# microsd.net
KiCad netlist of a schematic drawn in EAGLE
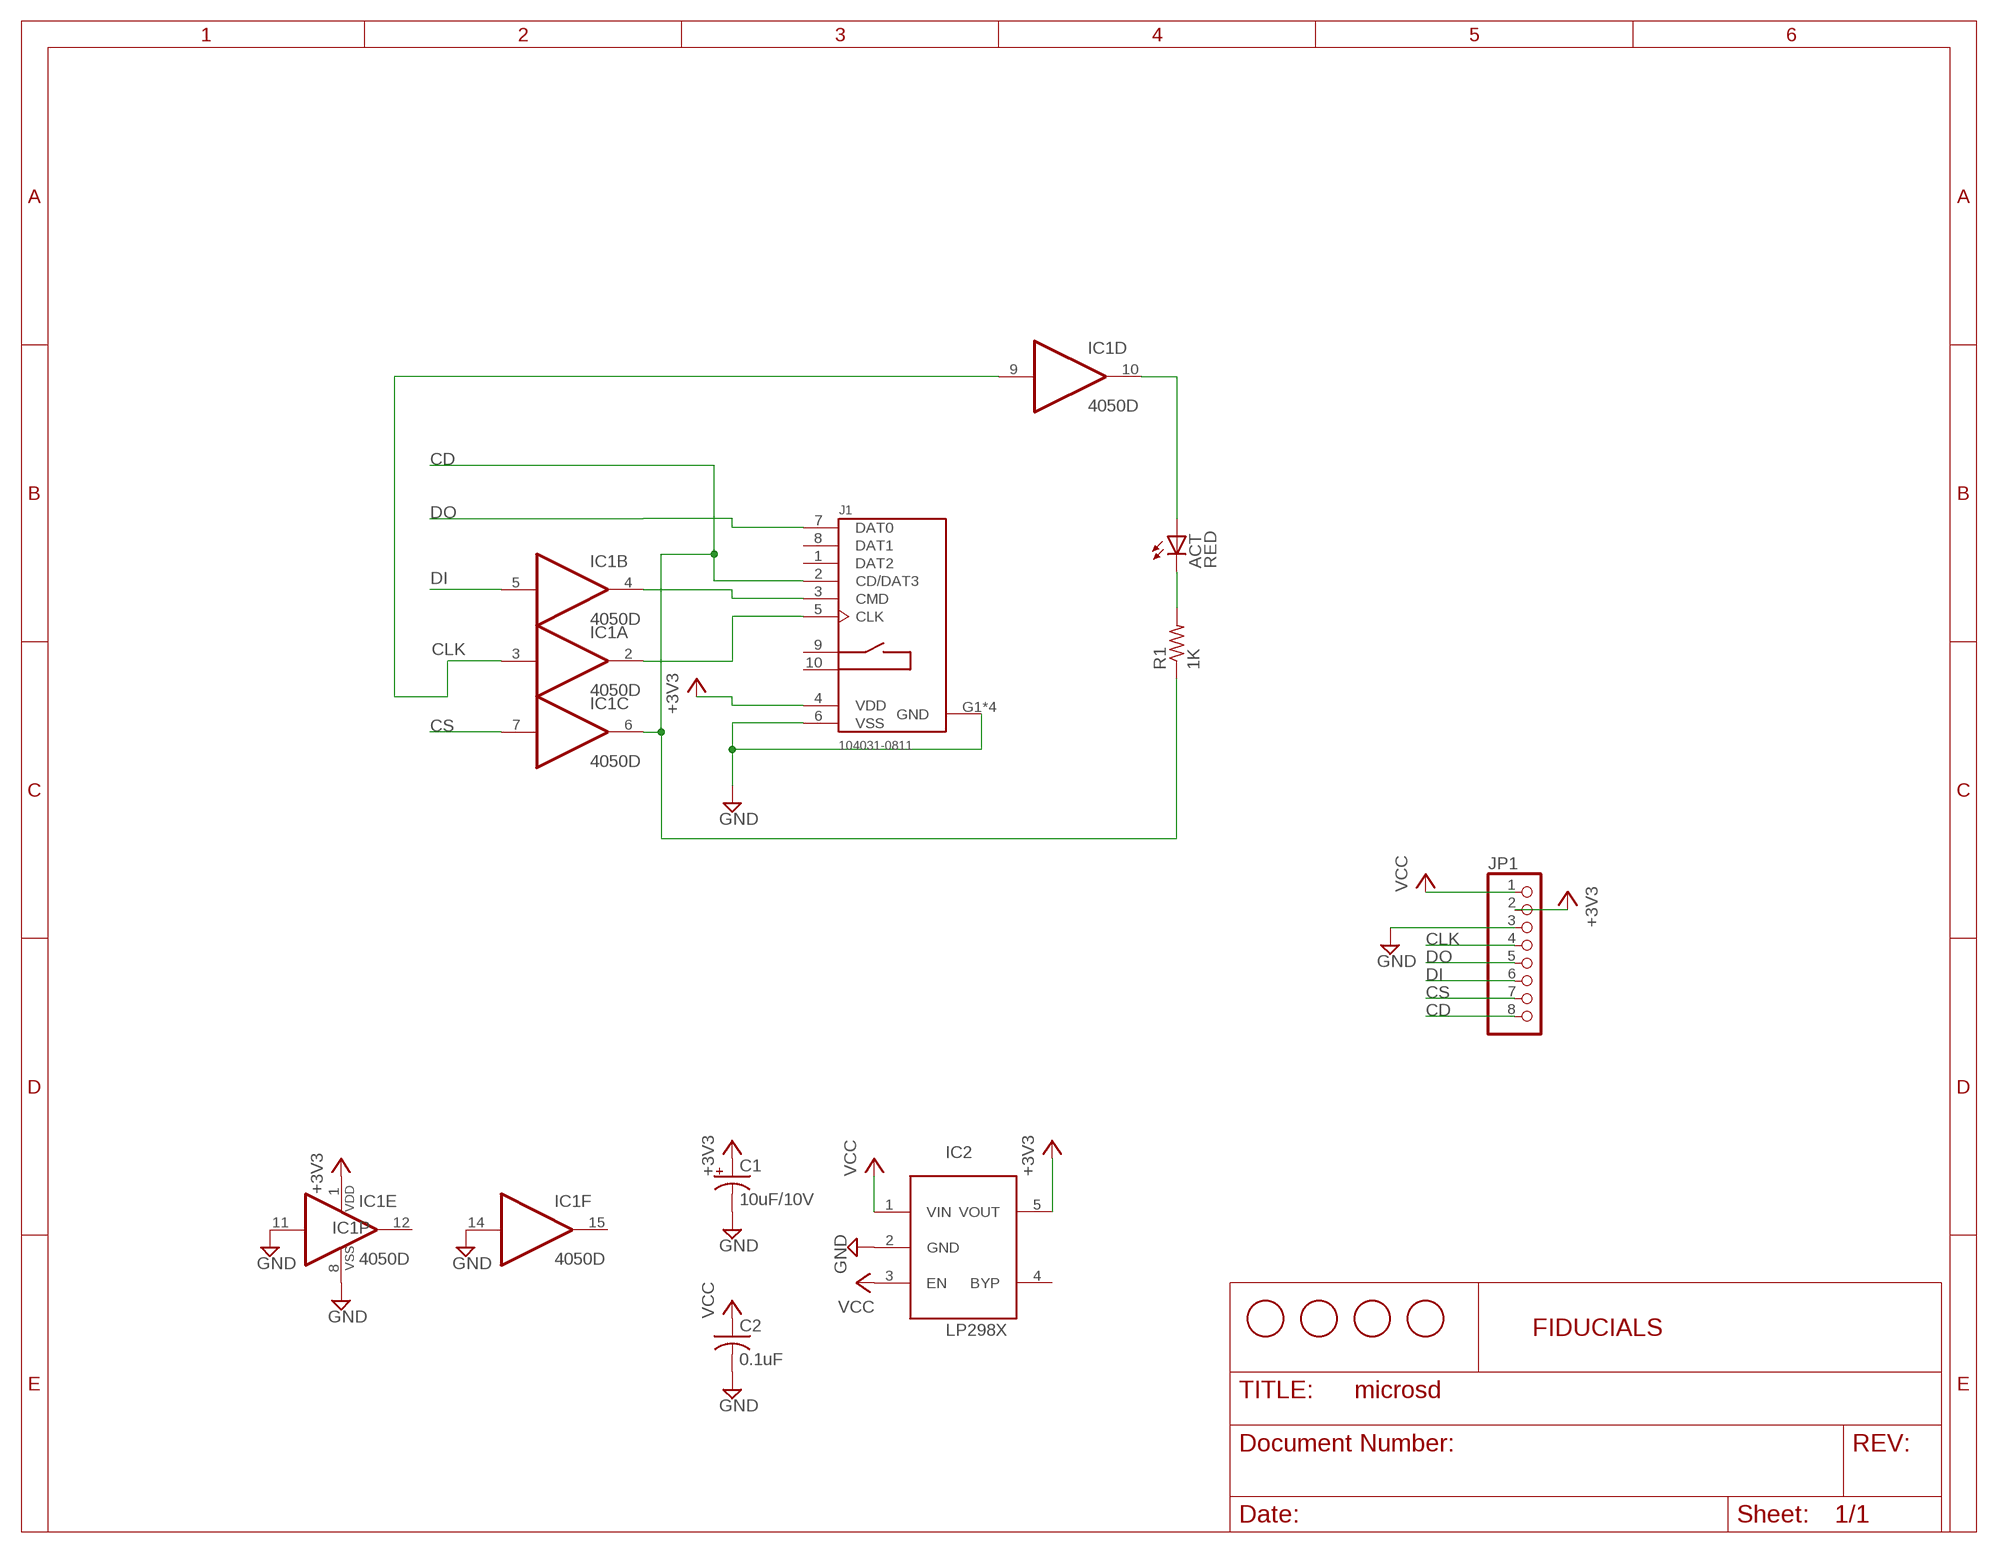
[diagram p0: schematic, sheet 1]

(export (version "E")
  (design (tool "Eeschema 10.0.6"))
  (components
    (comp (ref "ACT")
      (value "RED")
      (footprint "eagle-import:CHIP-LED0805")
      (libsource (lib "eagle-import") (part "LEDCHIP-LED0805"))
    )
    (comp (ref "C1")
      (value "10uF/10V")
      (footprint "eagle-import:A_3216-18R")
      (libsource (lib "eagle-import") (part "CPOL-USA/3216-18R"))
    )
    (comp (ref "C2")
      (value "0.1uF")
      (footprint "eagle-import:C0805K")
      (libsource (lib "eagle-import") (part "C-USC0805K"))
    )
    (comp (ref "IC1")
      (value "4050D")
      (footprint "eagle-import:SO16")
      (libsource (lib "eagle-import") (part "4050D"))
    )
    (comp (ref "IC2")
      (value "LP298XS")
      (footprint "eagle-import:SOT23-5L")
      (libsource (lib "eagle-import") (part "LP298XS"))
    )
    (comp (ref "J1")
      (value "104031-0811")
      (footprint "eagle-import:MOLEX_104031-0811")
      (fields (field (name "MF") "Molex"))
      (libsource (lib "eagle-import") (part "104031-0811"))
    )
    (comp (ref "JP1")
      (value "PINHD-1X8BIG")
      (footprint "eagle-import:1X08-BIG")
      (libsource (lib "eagle-import") (part "PINHD-1X8BIG"))
    )
    (comp (ref "R1")
      (value "1K")
      (footprint "eagle-import:R0805")
      (libsource (lib "eagle-import") (part "R-US_R0805"))
    )
    (comp (ref "U$1")
      (value "FIDUCIAL")
      (footprint "eagle-import:FIDUCIAL_1MM")
      (libsource (lib "eagle-import") (part "FIDUCIAL"))
    )
    (comp (ref "U$2")
      (value "FIDUCIAL")
      (footprint "eagle-import:FIDUCIAL_1MM")
      (libsource (lib "eagle-import") (part "FIDUCIAL"))
    )
    (comp (ref "U$3")
      (value "FIDUCIAL")
      (footprint "eagle-import:FIDUCIAL_1MM")
      (libsource (lib "eagle-import") (part "FIDUCIAL"))
    )
    (comp (ref "U$4")
      (value "FIDUCIAL")
      (footprint "eagle-import:FIDUCIAL_1MM")
      (libsource (lib "eagle-import") (part "FIDUCIAL"))
    )
  )
  (nets
    (net (code "1") (name "+3V3") (class "Default")
      (node (ref "C1") (pin "+") (pinfunction "+_+") (pintype "passive"))
      (node (ref "IC1") (pin "1") (pinfunction "VDD_1") (pintype "power_in"))
      (node (ref "IC2") (pin "5") (pinfunction "VOUT_5") (pintype "bidirectional"))
      (node (ref "J1") (pin "4") (pinfunction "VDD_4") (pintype "power_in"))
      (node (ref "JP1") (pin "2") (pinfunction "2_2") (pintype "passive"))
    )
    (net (code "2") (name "/CD") (class "Default")
      (node (ref "IC1") (pin "6") (pinfunction "O_6") (pintype "output"))
      (node (ref "J1") (pin "2") (pinfunction "CD/DAT3_2") (pintype "bidirectional"))
      (node (ref "JP1") (pin "8") (pinfunction "8_8") (pintype "passive"))
      (node (ref "R1") (pin "1") (pinfunction "1_1") (pintype "passive"))
    )
    (net (code "3") (name "/CLK") (class "Default")
      (node (ref "IC1") (pin "3") (pinfunction "I_3") (pintype "input"))
      (node (ref "IC1") (pin "9") (pinfunction "I_9") (pintype "input"))
      (node (ref "JP1") (pin "4") (pinfunction "4_4") (pintype "passive"))
    )
    (net (code "4") (name "/CS") (class "Default")
      (node (ref "IC1") (pin "7") (pinfunction "I_7") (pintype "input"))
      (node (ref "JP1") (pin "7") (pinfunction "7_7") (pintype "passive"))
    )
    (net (code "5") (name "/DI") (class "Default")
      (node (ref "IC1") (pin "5") (pinfunction "I_5") (pintype "input"))
      (node (ref "JP1") (pin "6") (pinfunction "6_6") (pintype "passive"))
    )
    (net (code "6") (name "/DO") (class "Default")
      (node (ref "J1") (pin "7") (pinfunction "DAT0_7") (pintype "bidirectional"))
      (node (ref "JP1") (pin "5") (pinfunction "5_5") (pintype "passive"))
    )
    (net (code "7") (name "GND") (class "Default")
      (node (ref "C1") (pin "-") (pinfunction "-_-") (pintype "passive"))
      (node (ref "C2") (pin "2") (pinfunction "2_2") (pintype "passive"))
      (node (ref "IC1") (pin "11") (pinfunction "I_11") (pintype "input"))
      (node (ref "IC1") (pin "14") (pinfunction "I_14") (pintype "input"))
      (node (ref "IC1") (pin "8") (pinfunction "VSS_8") (pintype "power_in"))
      (node (ref "IC2") (pin "2") (pinfunction "GND_2") (pintype "bidirectional"))
      (node (ref "J1") (pin "6") (pinfunction "VSS_6") (pintype "power_in"))
      (node (ref "J1") (pin "G1") (pinfunction "GND_G1") (pintype "power_in"))
      (node (ref "J1") (pin "G2") (pinfunction "GND_G2") (pintype "power_in"))
      (node (ref "J1") (pin "G3") (pinfunction "GND_G3") (pintype "power_in"))
      (node (ref "J1") (pin "G4") (pinfunction "GND_G4") (pintype "power_in"))
      (node (ref "JP1") (pin "3") (pinfunction "3_3") (pintype "passive"))
    )
    (net (code "8") (name "Net-(ACT-PadC)") (class "Default")
      (node (ref "ACT") (pin "C") (pinfunction "C_C") (pintype "passive"))
      (node (ref "R1") (pin "2") (pinfunction "2_2") (pintype "passive"))
    )
    (net (code "9") (name "Net-(IC1A-O)") (class "Default")
      (node (ref "IC1") (pin "2") (pinfunction "O_2") (pintype "output"))
      (node (ref "J1") (pin "5") (pinfunction "CLK_5") (pintype "input"))
    )
    (net (code "10") (name "Net-(IC1B-O)") (class "Default")
      (node (ref "IC1") (pin "4") (pinfunction "O_4") (pintype "output"))
      (node (ref "J1") (pin "3") (pinfunction "CMD_3") (pintype "input"))
    )
    (net (code "11") (name "Net-(IC1D-O)") (class "Default")
      (node (ref "ACT") (pin "A") (pinfunction "A_A") (pintype "passive"))
      (node (ref "IC1") (pin "10") (pinfunction "O_10") (pintype "output"))
    )
    (net (code "12") (name "VCC") (class "Default")
      (node (ref "C2") (pin "1") (pinfunction "1_1") (pintype "passive"))
      (node (ref "IC2") (pin "1") (pinfunction "VIN_1") (pintype "bidirectional"))
      (node (ref "IC2") (pin "3") (pinfunction "EN_3") (pintype "bidirectional"))
      (node (ref "JP1") (pin "1") (pinfunction "1_1") (pintype "passive"))
    )
    (net (code "13") (name "unconnected-(IC1E-O-Pad12)") (class "Default")
      (node (ref "IC1") (pin "12") (pinfunction "O_12") (pintype "output"))
    )
    (net (code "14") (name "unconnected-(IC1F-O-Pad15)") (class "Default")
      (node (ref "IC1") (pin "15") (pinfunction "O_15") (pintype "output"))
    )
    (net (code "15") (name "unconnected-(IC2-BYP-Pad4)") (class "Default")
      (node (ref "IC2") (pin "4") (pinfunction "BYP_4") (pintype "bidirectional"))
    )
    (net (code "16") (name "unconnected-(J1-CARD_DET1-Pad9)") (class "Default")
      (node (ref "J1") (pin "9") (pinfunction "CARD_DET1_9") (pintype "passive"))
    )
    (net (code "17") (name "unconnected-(J1-CARD_DET2-Pad10)") (class "Default")
      (node (ref "J1") (pin "10") (pinfunction "CARD_DET2_10") (pintype "passive"))
    )
    (net (code "18") (name "unconnected-(J1-DAT1-Pad8)") (class "Default")
      (node (ref "J1") (pin "8") (pinfunction "DAT1_8") (pintype "bidirectional"))
    )
    (net (code "19") (name "unconnected-(J1-DAT2-Pad1)") (class "Default")
      (node (ref "J1") (pin "1") (pinfunction "DAT2_1") (pintype "bidirectional"))
    )
  )
)
